# logger_-_V2.net
KiCad netlist of a schematic drawn in EAGLE
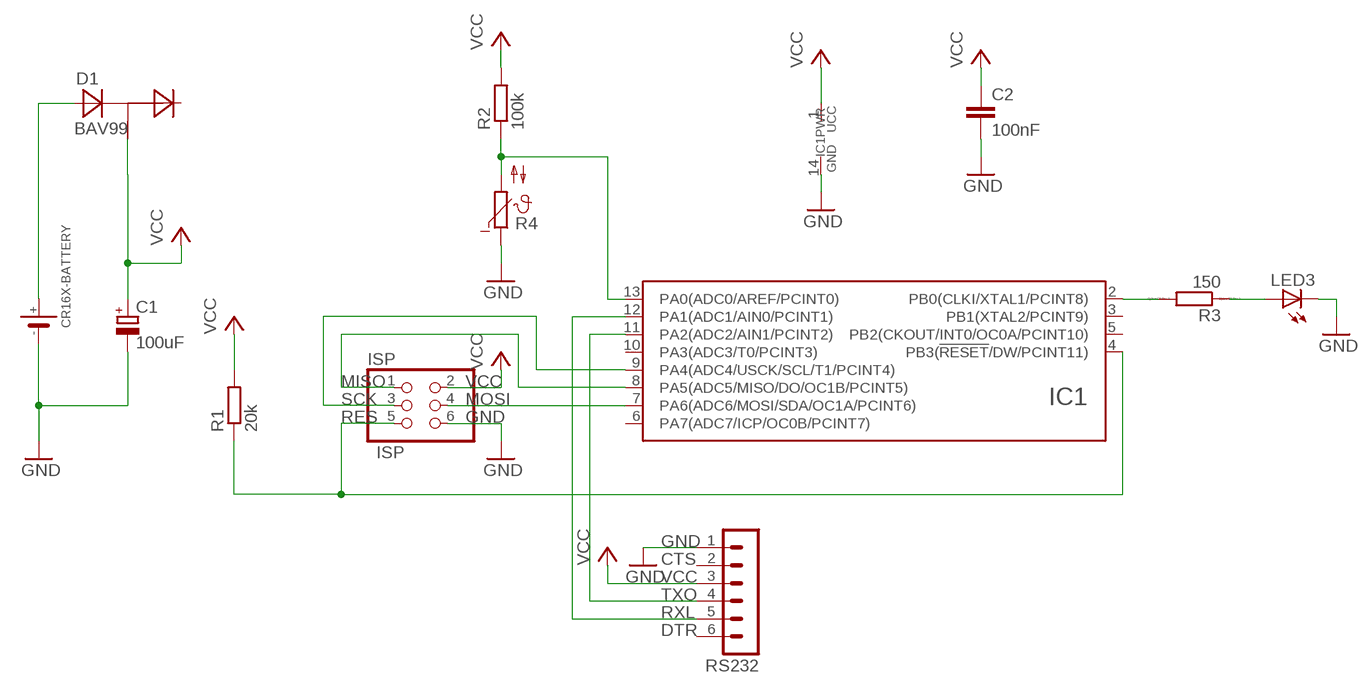
[diagram p0: schematic, sheet 1]

(export (version "E")
  (design (tool "Eeschema 10.0.6"))
  (components
    (comp (ref "C1")
      (value "100uF")
      (footprint "eagle-import:153CLV-0505")
      (libsource (lib "eagle-import") (part "CPOL-EU153CLV-0505"))
    )
    (comp (ref "C2")
      (value "100nF")
      (footprint "eagle-import:C1206K")
      (libsource (lib "eagle-import") (part "C-EUC1206K"))
    )
    (comp (ref "D1")
      (value "BAV99")
      (footprint "eagle-import:SOT-23")
      (libsource (lib "eagle-import") (part "BAV99"))
    )
    (comp (ref "IC1")
      (value "ATTINY24/44/84-SSU")
      (footprint "eagle-import:SOIC14")
      (fields (field (name "UCC") "VCC"))
      (libsource (lib "eagle-import") (part "ATTINY24/44/84-SSU"))
    )
    (comp (ref "ISP")
      (value "PINHD-2X3")
      (footprint "eagle-import:2X03")
      (libsource (lib "eagle-import") (part "PINHD-2X3"))
    )
    (comp (ref "LED3")
      (value "LED3MM")
      (footprint "eagle-import:LED3MM")
      (libsource (lib "eagle-import") (part "LED3MM"))
    )
    (comp (ref "R1")
      (value "20k")
      (footprint "eagle-import:R1206")
      (libsource (lib "eagle-import") (part "R-EU_R1206"))
    )
    (comp (ref "R2")
      (value "100k")
      (footprint "eagle-import:R1206")
      (libsource (lib "eagle-import") (part "R-EU_R1206"))
    )
    (comp (ref "R3")
      (value "150")
      (footprint "eagle-import:R1206")
      (libsource (lib "eagle-import") (part "RR1206"))
    )
    (comp (ref "R4")
      (value "NTC640")
      (footprint "eagle-import:P640")
      (libsource (lib "eagle-import") (part "NTC640"))
    )
    (comp (ref "RS232")
      (value "MA06-1")
      (footprint "eagle-import:MA06-1")
      (libsource (lib "eagle-import") (part "MA06-1"))
    )
    (comp (ref "U$1")
      (value "CR16X-BATTERY")
      (footprint "eagle-import:16MM-BATTERY-HOLDER")
      (libsource (lib "eagle-import") (part "CR16X-BATTERY"))
    )
  )
  (nets
    (net (code "1") (name "/MISO") (class "Default")
      (node (ref "IC1") (pin "8") (pinfunction "PA5(ADC5/MISO/DO/OC1B/PCINT5)_8") (pintype "bidirectional"))
      (node (ref "ISP") (pin "1") (pinfunction "1_1") (pintype "passive"))
    )
    (net (code "2") (name "/MOSI") (class "Default")
      (node (ref "IC1") (pin "7") (pinfunction "PA6(ADC6/MOSI/SDA/OC1A/PCINT6)_7") (pintype "bidirectional"))
      (node (ref "ISP") (pin "4") (pinfunction "4_4") (pintype "passive"))
    )
    (net (code "3") (name "/RES") (class "Default")
      (node (ref "IC1") (pin "4") (pinfunction "PB3(~{RESET}/DW/PCINT11)_4") (pintype "bidirectional"))
      (node (ref "ISP") (pin "5") (pinfunction "5_5") (pintype "passive"))
      (node (ref "R1") (pin "1") (pinfunction "1_1") (pintype "passive"))
    )
    (net (code "4") (name "/SCK") (class "Default")
      (node (ref "IC1") (pin "9") (pinfunction "PA4(ADC4/USCK/SCL/T1/PCINT4)_9") (pintype "bidirectional"))
      (node (ref "ISP") (pin "3") (pinfunction "3_3") (pintype "passive"))
    )
    (net (code "5") (name "GND") (class "Default")
      (node (ref "C1") (pin "-") (pinfunction "-_-") (pintype "passive"))
      (node (ref "C2") (pin "2") (pinfunction "2_2") (pintype "passive"))
      (node (ref "IC1") (pin "14") (pinfunction "GND_14") (pintype "power_in"))
      (node (ref "ISP") (pin "6") (pinfunction "6_6") (pintype "passive"))
      (node (ref "LED3") (pin "K") (pinfunction "C_K") (pintype "passive"))
      (node (ref "R4") (pin "1") (pinfunction "1_1") (pintype "passive"))
      (node (ref "RS232") (pin "1") (pinfunction "1_1") (pintype "passive"))
      (node (ref "U$1") (pin "P$1") (pinfunction "P$2_P$1") (pintype "bidirectional"))
    )
    (net (code "6") (name "Net-(D1-A)") (class "Default")
      (node (ref "D1") (pin "3") (pinfunction "A_3") (pintype "passive"))
      (node (ref "U$1") (pin "P$2") (pinfunction "P$1_P$2") (pintype "bidirectional"))
    )
    (net (code "7") (name "Net-(IC1A-PA0(ADC0{slash}AREF{slash}PCINT0))") (class "Default")
      (node (ref "IC1") (pin "13") (pinfunction "PA0(ADC0/AREF/PCINT0)_13") (pintype "bidirectional"))
      (node (ref "R2") (pin "1") (pinfunction "1_1") (pintype "passive"))
      (node (ref "R4") (pin "2") (pinfunction "2_2") (pintype "passive"))
    )
    (net (code "8") (name "Net-(IC1A-PA1(ADC1{slash}AIN0{slash}PCINT1))") (class "Default")
      (node (ref "IC1") (pin "12") (pinfunction "PA1(ADC1/AIN0/PCINT1)_12") (pintype "bidirectional"))
      (node (ref "RS232") (pin "5") (pinfunction "5_5") (pintype "passive"))
    )
    (net (code "9") (name "Net-(IC1A-PA2(ADC2{slash}AIN1{slash}PCINT2))") (class "Default")
      (node (ref "IC1") (pin "11") (pinfunction "PA2(ADC2/AIN1/PCINT2)_11") (pintype "bidirectional"))
      (node (ref "RS232") (pin "4") (pinfunction "4_4") (pintype "passive"))
    )
    (net (code "10") (name "Net-(IC1A-PB0(CLKI{slash}XTAL1{slash}PCINT8))") (class "Default")
      (node (ref "IC1") (pin "2") (pinfunction "PB0(CLKI/XTAL1/PCINT8)_2") (pintype "bidirectional"))
      (node (ref "R3") (pin "2") (pinfunction "2_2") (pintype "passive"))
    )
    (net (code "11") (name "Net-(LED3-PadA)") (class "Default")
      (node (ref "LED3") (pin "A") (pinfunction "A_A") (pintype "passive"))
      (node (ref "R3") (pin "1") (pinfunction "1_1") (pintype "passive"))
    )
    (net (code "12") (name "VCC") (class "Default")
      (node (ref "C1") (pin "+") (pinfunction "+_+") (pintype "passive"))
      (node (ref "C2") (pin "1") (pinfunction "1_1") (pintype "passive"))
      (node (ref "D1") (pin "1") (pinfunction "M_1") (pintype "passive"))
      (node (ref "IC1") (pin "1") (pinfunction "UCC_1") (pintype "power_in"))
      (node (ref "ISP") (pin "2") (pinfunction "2_2") (pintype "passive"))
      (node (ref "R1") (pin "2") (pinfunction "2_2") (pintype "passive"))
      (node (ref "R2") (pin "2") (pinfunction "2_2") (pintype "passive"))
      (node (ref "RS232") (pin "3") (pinfunction "3_3") (pintype "passive"))
    )
    (net (code "13") (name "unconnected-(D1-C-Pad2)") (class "Default")
      (node (ref "D1") (pin "2") (pinfunction "C_2") (pintype "passive"))
    )
    (net (code "14") (name "unconnected-(IC1A-PA3(ADC3{slash}T0{slash}PCINT3)-Pad10)") (class "Default")
      (node (ref "IC1") (pin "10") (pinfunction "PA3(ADC3/T0/PCINT3)_10") (pintype "bidirectional"))
    )
    (net (code "15") (name "unconnected-(IC1A-PA7(ADC7{slash}ICP{slash}OC0B{slash}PCINT7)-Pad6)") (class "Default")
      (node (ref "IC1") (pin "6") (pinfunction "PA7(ADC7/ICP/OC0B/PCINT7)_6") (pintype "bidirectional"))
    )
    (net (code "16") (name "unconnected-(IC1A-PB1(XTAL2{slash}PCINT9)-Pad3)") (class "Default")
      (node (ref "IC1") (pin "3") (pinfunction "PB1(XTAL2/PCINT9)_3") (pintype "bidirectional"))
    )
    (net (code "17") (name "unconnected-(IC1A-PB2(CKOUT{slash}INT0{slash}OC0A{slash}PCINT10)-Pad5)") (class "Default")
      (node (ref "IC1") (pin "5") (pinfunction "PB2(CKOUT/INT0/OC0A/PCINT10)_5") (pintype "bidirectional"))
    )
    (net (code "18") (name "unconnected-(RS232-Pad2)") (class "Default")
      (node (ref "RS232") (pin "2") (pinfunction "2_2") (pintype "passive"))
    )
    (net (code "19") (name "unconnected-(RS232-Pad6)") (class "Default")
      (node (ref "RS232") (pin "6") (pinfunction "6_6") (pintype "passive"))
    )
  )
)
